# MOTORS.net
KiCad netlist of a schematic drawn in Altium Designer
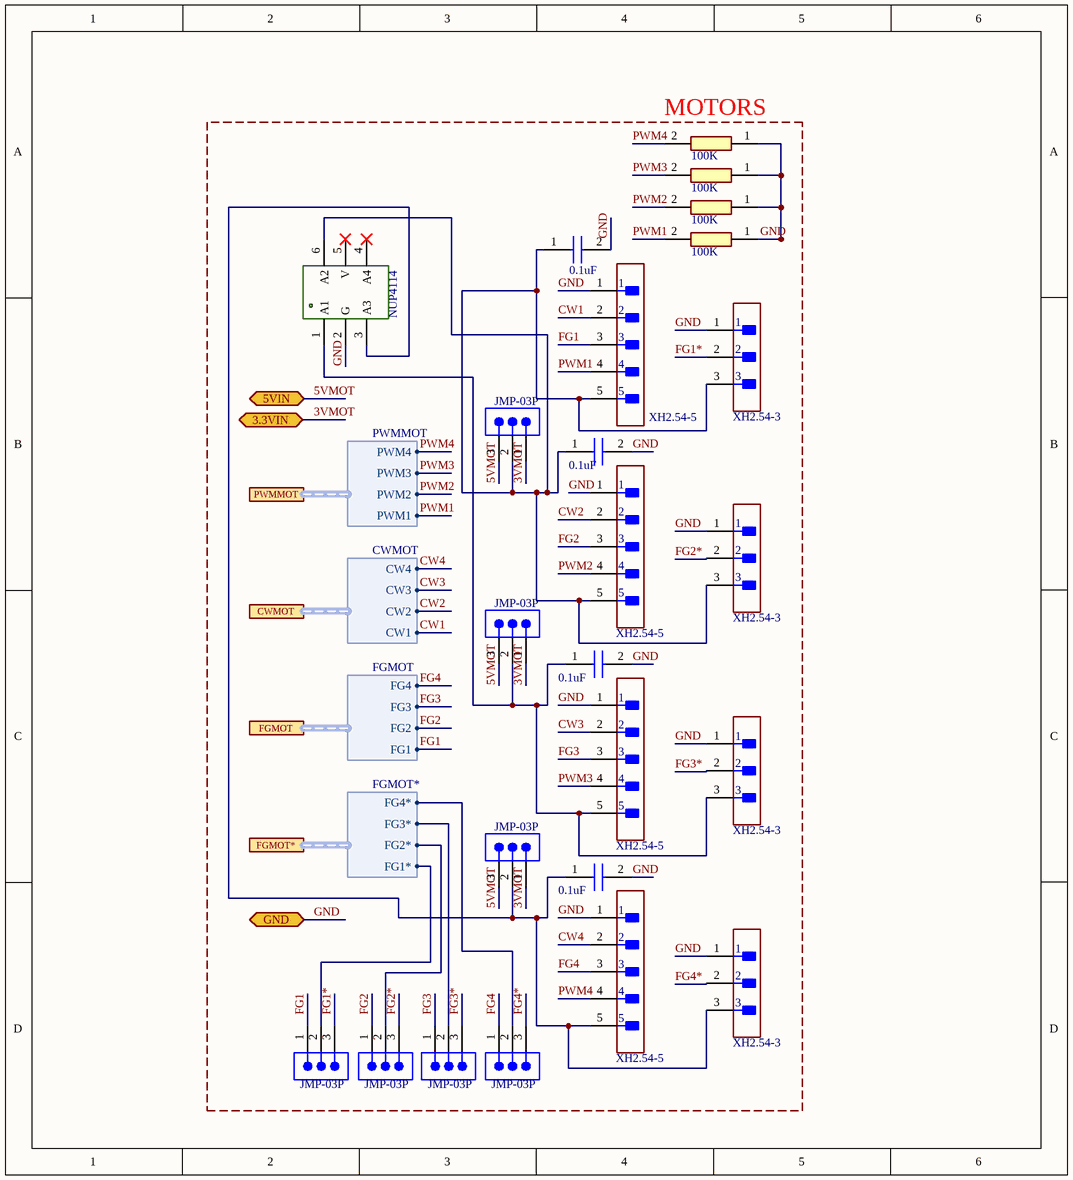
[diagram p0: MOTORS.SchDoc]

(export (version "E")
  (design (tool "Eeschema 10.0.6"))
  (components
    (comp (ref "CAPMOT1")
      (value "0.1uF")
      (footprint "CAP0805")
      (description "CAP-SMD0805")
      (libsource (lib "Components_Robots") (part "CAP0805"))
    )
    (comp (ref "CAPMOT2")
      (value "0.1uF")
      (footprint "CAP0805")
      (description "CAP-SMD0805")
      (libsource (lib "Components_Robots") (part "CAP0805"))
    )
    (comp (ref "CAPMOT3")
      (value "0.1uF")
      (footprint "CAP0805")
      (description "CAP-SMD0805")
      (libsource (lib "Components_Robots") (part "CAP0805"))
    )
    (comp (ref "CAPMOT4")
      (value "0.1uF")
      (footprint "CAP0805")
      (description "CAP-SMD0805")
      (libsource (lib "Components_Robots") (part "CAP0805"))
    )
    (comp (ref "JMPFG1")
      (value "JMP-03P")
      (footprint "JMP-03P")
      (description "PLS-1x3")
      (libsource (lib "Components_Robots") (part "JMP-03P"))
    )
    (comp (ref "JMPFG2")
      (value "JMP-03P")
      (footprint "JMP-03P")
      (description "PLS-1x3")
      (libsource (lib "Components_Robots") (part "JMP-03P"))
    )
    (comp (ref "JMPFG3")
      (value "JMP-03P")
      (footprint "JMP-03P")
      (description "PLS-1x3")
      (libsource (lib "Components_Robots") (part "JMP-03P"))
    )
    (comp (ref "JMPFG4")
      (value "JMP-03P")
      (footprint "JMP-03P")
      (description "PLS-1x3")
      (libsource (lib "Components_Robots") (part "JMP-03P"))
    )
    (comp (ref "JMPMOT2")
      (value "JMP-03P")
      (footprint "JMP-03P")
      (description "PLS-1x3")
      (libsource (lib "Components_Robots") (part "JMP-03P"))
    )
    (comp (ref "JMPMOT3")
      (value "JMP-03P")
      (footprint "JMP-03P")
      (description "PLS-1x3")
      (libsource (lib "Components_Robots") (part "JMP-03P"))
    )
    (comp (ref "JMPMOT4")
      (value "JMP-03P")
      (footprint "JMP-03P")
      (description "PLS-1x3")
      (libsource (lib "Components_Robots") (part "JMP-03P"))
    )
    (comp (ref "NUPMOT")
      (value "NUP4114")
      (footprint "NUP4114")
      (description "NUP4114HMR6T1G")
      (libsource (lib "Components_Robots") (part "NUP4114"))
    )
    (comp (ref "RESPWM1")
      (value "100K")
      (footprint "RES0805")
      (description "RES-SMD0805")
      (libsource (lib "Components_Robots") (part "RES0805"))
    )
    (comp (ref "RESPWM2")
      (value "100K")
      (footprint "RES0805")
      (description "RES-SMD0805")
      (libsource (lib "Components_Robots") (part "RES0805"))
    )
    (comp (ref "RESPWM3")
      (value "100K")
      (footprint "RES0805")
      (description "RES-SMD0805")
      (libsource (lib "Components_Robots") (part "RES0805"))
    )
    (comp (ref "RESPWM4")
      (value "100K")
      (footprint "RES0805")
      (description "RES-SMD0805")
      (libsource (lib "Components_Robots") (part "RES0805"))
    )
    (comp (ref "XH3MOT1")
      (value "XH2.54-3")
      (footprint "XH2.54-3")
      (description "JST XH2.54-3pin")
      (libsource (lib "Components_Robots") (part "XH2.54-3"))
    )
    (comp (ref "XH3MOT2")
      (value "XH2.54-3")
      (footprint "XH2.54-3")
      (description "JST XH2.54-3pin")
      (libsource (lib "Components_Robots") (part "XH2.54-3"))
    )
    (comp (ref "XH3MOT3")
      (value "XH2.54-3")
      (footprint "XH2.54-3")
      (description "JST XH2.54-3pin")
      (libsource (lib "Components_Robots") (part "XH2.54-3"))
    )
    (comp (ref "XH3MOT4")
      (value "XH2.54-3")
      (footprint "XH2.54-3")
      (description "JST XH2.54-3pin")
      (libsource (lib "Components_Robots") (part "XH2.54-3"))
    )
    (comp (ref "XH5MOT1")
      (value "XH2.54-5")
      (footprint "XH2.54-5")
      (description "JST XH2.54-5pin")
      (libsource (lib "Components_Robots") (part "XH2.54-5"))
    )
    (comp (ref "XH5MOT2")
      (value "XH2.54-5")
      (footprint "XH2.54-5")
      (description "JST XH2.54-5pin")
      (libsource (lib "Components_Robots") (part "XH2.54-5"))
    )
    (comp (ref "XH5MOT3")
      (value "XH2.54-5")
      (footprint "XH2.54-5")
      (description "JST XH2.54-5pin")
      (libsource (lib "Components_Robots") (part "XH2.54-5"))
    )
    (comp (ref "XH5MOT4")
      (value "XH2.54-5")
      (footprint "XH2.54-5")
      (description "JST XH2.54-5pin")
      (libsource (lib "Components_Robots") (part "XH2.54-5"))
    )
  )
  (nets
    (net (code "5") (name "/3VMOT") (class "Default")
      (node (ref "JMPMOT2") (pin "1") (pinfunction "1_1") (pintype "passive"))
      (node (ref "JMPMOT3") (pin "1") (pinfunction "1_1") (pintype "passive"))
      (node (ref "JMPMOT4") (pin "1") (pinfunction "1_1") (pintype "passive"))
    )
    (net (code "6") (name "/5VMOT") (class "Default")
      (node (ref "JMPMOT2") (pin "3") (pinfunction "3_3") (pintype "passive"))
      (node (ref "JMPMOT3") (pin "3") (pinfunction "3_3") (pintype "passive"))
      (node (ref "JMPMOT4") (pin "3") (pinfunction "3_3") (pintype "passive"))
    )
    (net (code "7") (name "/CW1") (class "Default")
      (node (ref "XH5MOT1") (pin "2") (pinfunction "2_2") (pintype "passive"))
    )
    (net (code "8") (name "/CW2") (class "Default")
      (node (ref "XH5MOT2") (pin "2") (pinfunction "2_2") (pintype "passive"))
    )
    (net (code "9") (name "/CW3") (class "Default")
      (node (ref "XH5MOT3") (pin "2") (pinfunction "2_2") (pintype "passive"))
    )
    (net (code "10") (name "/CW4") (class "Default")
      (node (ref "XH5MOT4") (pin "2") (pinfunction "2_2") (pintype "passive"))
    )
    (net (code "11") (name "/FG1") (class "Default")
      (node (ref "JMPFG1") (pin "1") (pinfunction "1_1") (pintype "passive"))
      (node (ref "XH5MOT1") (pin "3") (pinfunction "3_3") (pintype "passive"))
    )
    (net (code "12") (name "/FG1*") (class "Default")
      (node (ref "JMPFG1") (pin "3") (pinfunction "3_3") (pintype "passive"))
      (node (ref "XH3MOT1") (pin "2") (pinfunction "2_2") (pintype "passive"))
    )
    (net (code "13") (name "/FG2") (class "Default")
      (node (ref "JMPFG2") (pin "1") (pinfunction "1_1") (pintype "passive"))
      (node (ref "XH5MOT2") (pin "3") (pinfunction "3_3") (pintype "passive"))
    )
    (net (code "14") (name "/FG2*") (class "Default")
      (node (ref "JMPFG2") (pin "3") (pinfunction "3_3") (pintype "passive"))
      (node (ref "XH3MOT2") (pin "2") (pinfunction "2_2") (pintype "passive"))
    )
    (net (code "15") (name "/FG3") (class "Default")
      (node (ref "JMPFG3") (pin "1") (pinfunction "1_1") (pintype "passive"))
      (node (ref "XH5MOT3") (pin "3") (pinfunction "3_3") (pintype "passive"))
    )
    (net (code "16") (name "/FG3*") (class "Default")
      (node (ref "JMPFG3") (pin "3") (pinfunction "3_3") (pintype "passive"))
      (node (ref "XH3MOT3") (pin "2") (pinfunction "2_2") (pintype "passive"))
    )
    (net (code "17") (name "/FG4") (class "Default")
      (node (ref "JMPFG4") (pin "1") (pinfunction "1_1") (pintype "passive"))
      (node (ref "XH5MOT4") (pin "3") (pinfunction "3_3") (pintype "passive"))
    )
    (net (code "18") (name "/FG4*") (class "Default")
      (node (ref "JMPFG4") (pin "3") (pinfunction "3_3") (pintype "passive"))
      (node (ref "XH3MOT4") (pin "2") (pinfunction "2_2") (pintype "passive"))
    )
    (net (code "19") (name "/GND") (class "Default")
      (node (ref "CAPMOT1") (pin "2") (pinfunction "2_2") (pintype "passive"))
      (node (ref "CAPMOT2") (pin "2") (pinfunction "2_2") (pintype "passive"))
      (node (ref "CAPMOT3") (pin "2") (pinfunction "2_2") (pintype "passive"))
      (node (ref "CAPMOT4") (pin "2") (pinfunction "2_2") (pintype "passive"))
      (node (ref "NUPMOT") (pin "2") (pinfunction "G_2") (pintype "passive"))
      (node (ref "RESPWM1") (pin "1") (pinfunction "1_1") (pintype "passive"))
      (node (ref "RESPWM2") (pin "1") (pinfunction "1_1") (pintype "passive"))
      (node (ref "RESPWM3") (pin "1") (pinfunction "1_1") (pintype "passive"))
      (node (ref "RESPWM4") (pin "1") (pinfunction "1_1") (pintype "passive"))
      (node (ref "XH3MOT1") (pin "1") (pinfunction "1_1") (pintype "passive"))
      (node (ref "XH3MOT2") (pin "1") (pinfunction "1_1") (pintype "passive"))
      (node (ref "XH3MOT3") (pin "1") (pinfunction "1_1") (pintype "passive"))
      (node (ref "XH3MOT4") (pin "1") (pinfunction "1_1") (pintype "passive"))
      (node (ref "XH5MOT1") (pin "1") (pinfunction "1_1") (pintype "passive"))
      (node (ref "XH5MOT2") (pin "1") (pinfunction "1_1") (pintype "passive"))
      (node (ref "XH5MOT3") (pin "1") (pinfunction "1_1") (pintype "passive"))
      (node (ref "XH5MOT4") (pin "1") (pinfunction "1_1") (pintype "passive"))
    )
    (net (code "20") (name "/PWM1") (class "Default")
      (node (ref "RESPWM2") (pin "2") (pinfunction "2_2") (pintype "passive"))
      (node (ref "XH5MOT1") (pin "4") (pinfunction "4_4") (pintype "passive"))
    )
    (net (code "21") (name "/PWM2") (class "Default")
      (node (ref "RESPWM1") (pin "2") (pinfunction "2_2") (pintype "passive"))
      (node (ref "XH5MOT2") (pin "4") (pinfunction "4_4") (pintype "passive"))
    )
    (net (code "22") (name "/PWM3") (class "Default")
      (node (ref "RESPWM3") (pin "2") (pinfunction "2_2") (pintype "passive"))
      (node (ref "XH5MOT3") (pin "4") (pinfunction "4_4") (pintype "passive"))
    )
    (net (code "23") (name "/PWM4") (class "Default")
      (node (ref "RESPWM4") (pin "2") (pinfunction "2_2") (pintype "passive"))
      (node (ref "XH5MOT4") (pin "4") (pinfunction "4_4") (pintype "passive"))
    )
    (net (code "28") (name "Net-(NUPMOT-A1)") (class "Default")
      (node (ref "CAPMOT3") (pin "1") (pinfunction "1_1") (pintype "passive"))
      (node (ref "JMPMOT3") (pin "2") (pinfunction "2_2") (pintype "passive"))
      (node (ref "NUPMOT") (pin "1") (pinfunction "A1_1") (pintype "passive"))
      (node (ref "XH3MOT3") (pin "3") (pinfunction "3_3") (pintype "passive"))
      (node (ref "XH5MOT3") (pin "5") (pinfunction "5_5") (pintype "passive"))
    )
    (net (code "29") (name "Net-(NUPMOT-A2)") (class "Default")
      (node (ref "CAPMOT1") (pin "1") (pinfunction "1_1") (pintype "passive"))
      (node (ref "CAPMOT2") (pin "1") (pinfunction "1_1") (pintype "passive"))
      (node (ref "JMPMOT2") (pin "2") (pinfunction "2_2") (pintype "passive"))
      (node (ref "NUPMOT") (pin "6") (pinfunction "A2_6") (pintype "passive"))
      (node (ref "XH3MOT1") (pin "3") (pinfunction "3_3") (pintype "passive"))
      (node (ref "XH3MOT2") (pin "3") (pinfunction "3_3") (pintype "passive"))
      (node (ref "XH5MOT1") (pin "5") (pinfunction "5_5") (pintype "passive"))
      (node (ref "XH5MOT2") (pin "5") (pinfunction "5_5") (pintype "passive"))
    )
    (net (code "30") (name "Net-(NUPMOT-A3)") (class "Default")
      (node (ref "CAPMOT4") (pin "1") (pinfunction "1_1") (pintype "passive"))
      (node (ref "JMPMOT4") (pin "2") (pinfunction "2_2") (pintype "passive"))
      (node (ref "NUPMOT") (pin "3") (pinfunction "A3_3") (pintype "passive"))
      (node (ref "XH3MOT4") (pin "3") (pinfunction "3_3") (pintype "passive"))
      (node (ref "XH5MOT4") (pin "5") (pinfunction "5_5") (pintype "passive"))
    )
    (net (code "31") (name "unconnected-(JMPFG1-Pad2)") (class "Default")
      (node (ref "JMPFG1") (pin "2") (pinfunction "2_2") (pintype "passive"))
    )
    (net (code "32") (name "unconnected-(JMPFG2-Pad2)") (class "Default")
      (node (ref "JMPFG2") (pin "2") (pinfunction "2_2") (pintype "passive"))
    )
    (net (code "33") (name "unconnected-(JMPFG3-Pad2)") (class "Default")
      (node (ref "JMPFG3") (pin "2") (pinfunction "2_2") (pintype "passive"))
    )
    (net (code "34") (name "unconnected-(JMPFG4-Pad2)") (class "Default")
      (node (ref "JMPFG4") (pin "2") (pinfunction "2_2") (pintype "passive"))
    )
    (net (code "35") (name "unconnected-(NUPMOT-A4-Pad4)") (class "Default")
      (node (ref "NUPMOT") (pin "4") (pinfunction "A4_4") (pintype "passive+no_connect"))
    )
    (net (code "36") (name "unconnected-(NUPMOT-V-Pad5)") (class "Default")
      (node (ref "NUPMOT") (pin "5") (pinfunction "V_5") (pintype "passive+no_connect"))
    )
  )
)
